# fireflies.net
KiCad netlist of a schematic drawn in EAGLE
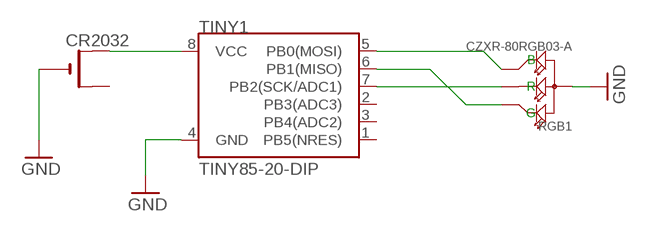
[diagram p0: schematic, sheet 1]

(export (version "E")
  (design (tool "Eeschema 10.0.6"))
  (components
    (comp (ref "CR2032")
      (value "CR2032SMT")
      (footprint "eagle-import:CR2032-SMD")
      (libsource (lib "eagle-import") (part "CR2032SMT"))
    )
    (comp (ref "RGB1")
      (value "CZXR-80RGB03-A")
      (footprint "eagle-import:LED4-2.0-D8.0MM")
      (libsource (lib "eagle-import") (part "DIP-LED-RGB-COMMON-ANODE(4P-D8MM)"))
    )
    (comp (ref "TINY1")
      (value "TINY85-20-DIP")
      (footprint "eagle-import:DIP08")
      (libsource (lib "eagle-import") (part "ATTINY45TINY85-20-DIP"))
    )
  )
  (nets
    (net (code "1") (name "GND") (class "Default")
      (node (ref "CR2032") (pin "-") (pinfunction "-_-") (pintype "passive"))
      (node (ref "RGB1") (pin "2") (pinfunction "+_2") (pintype "bidirectional"))
      (node (ref "TINY1") (pin "4") (pinfunction "GND_4") (pintype "bidirectional"))
    )
    (net (code "2") (name "Net-(CR2032-+)") (class "Default")
      (node (ref "CR2032") (pin "+$1") (pinfunction "+_+$1") (pintype "passive"))
      (node (ref "TINY1") (pin "8") (pinfunction "VCC_8") (pintype "bidirectional"))
    )
    (net (code "3") (name "Net-(RGB1-B)") (class "Default")
      (node (ref "RGB1") (pin "4") (pinfunction "B_4") (pintype "bidirectional"))
      (node (ref "TINY1") (pin "5") (pinfunction "PB0(MOSI)_5") (pintype "bidirectional"))
    )
    (net (code "4") (name "Net-(RGB1-G)") (class "Default")
      (node (ref "RGB1") (pin "3") (pinfunction "G_3") (pintype "bidirectional"))
      (node (ref "TINY1") (pin "6") (pinfunction "PB1(MISO)_6") (pintype "bidirectional"))
    )
    (net (code "5") (name "Net-(RGB1-R)") (class "Default")
      (node (ref "RGB1") (pin "1") (pinfunction "R_1") (pintype "bidirectional"))
      (node (ref "TINY1") (pin "7") (pinfunction "PB2(SCK/ADC1)_7") (pintype "bidirectional"))
    )
    (net (code "6") (name "unconnected-(CR2032-+1-Pad+$2)") (class "Default")
      (node (ref "CR2032") (pin "+$2") (pinfunction "+1_+$2") (pintype "passive"))
    )
    (net (code "7") (name "unconnected-(TINY1-PB3(ADC3)-Pad2)") (class "Default")
      (node (ref "TINY1") (pin "2") (pinfunction "PB3(ADC3)_2") (pintype "bidirectional"))
    )
    (net (code "8") (name "unconnected-(TINY1-PB4(ADC2)-Pad3)") (class "Default")
      (node (ref "TINY1") (pin "3") (pinfunction "PB4(ADC2)_3") (pintype "bidirectional"))
    )
    (net (code "9") (name "unconnected-(TINY1-PB5(NRES)-Pad1)") (class "Default")
      (node (ref "TINY1") (pin "1") (pinfunction "PB5(NRES)_1") (pintype "bidirectional"))
    )
  )
)
